# stm8.net
KiCad netlist of a schematic drawn in Altium Designer
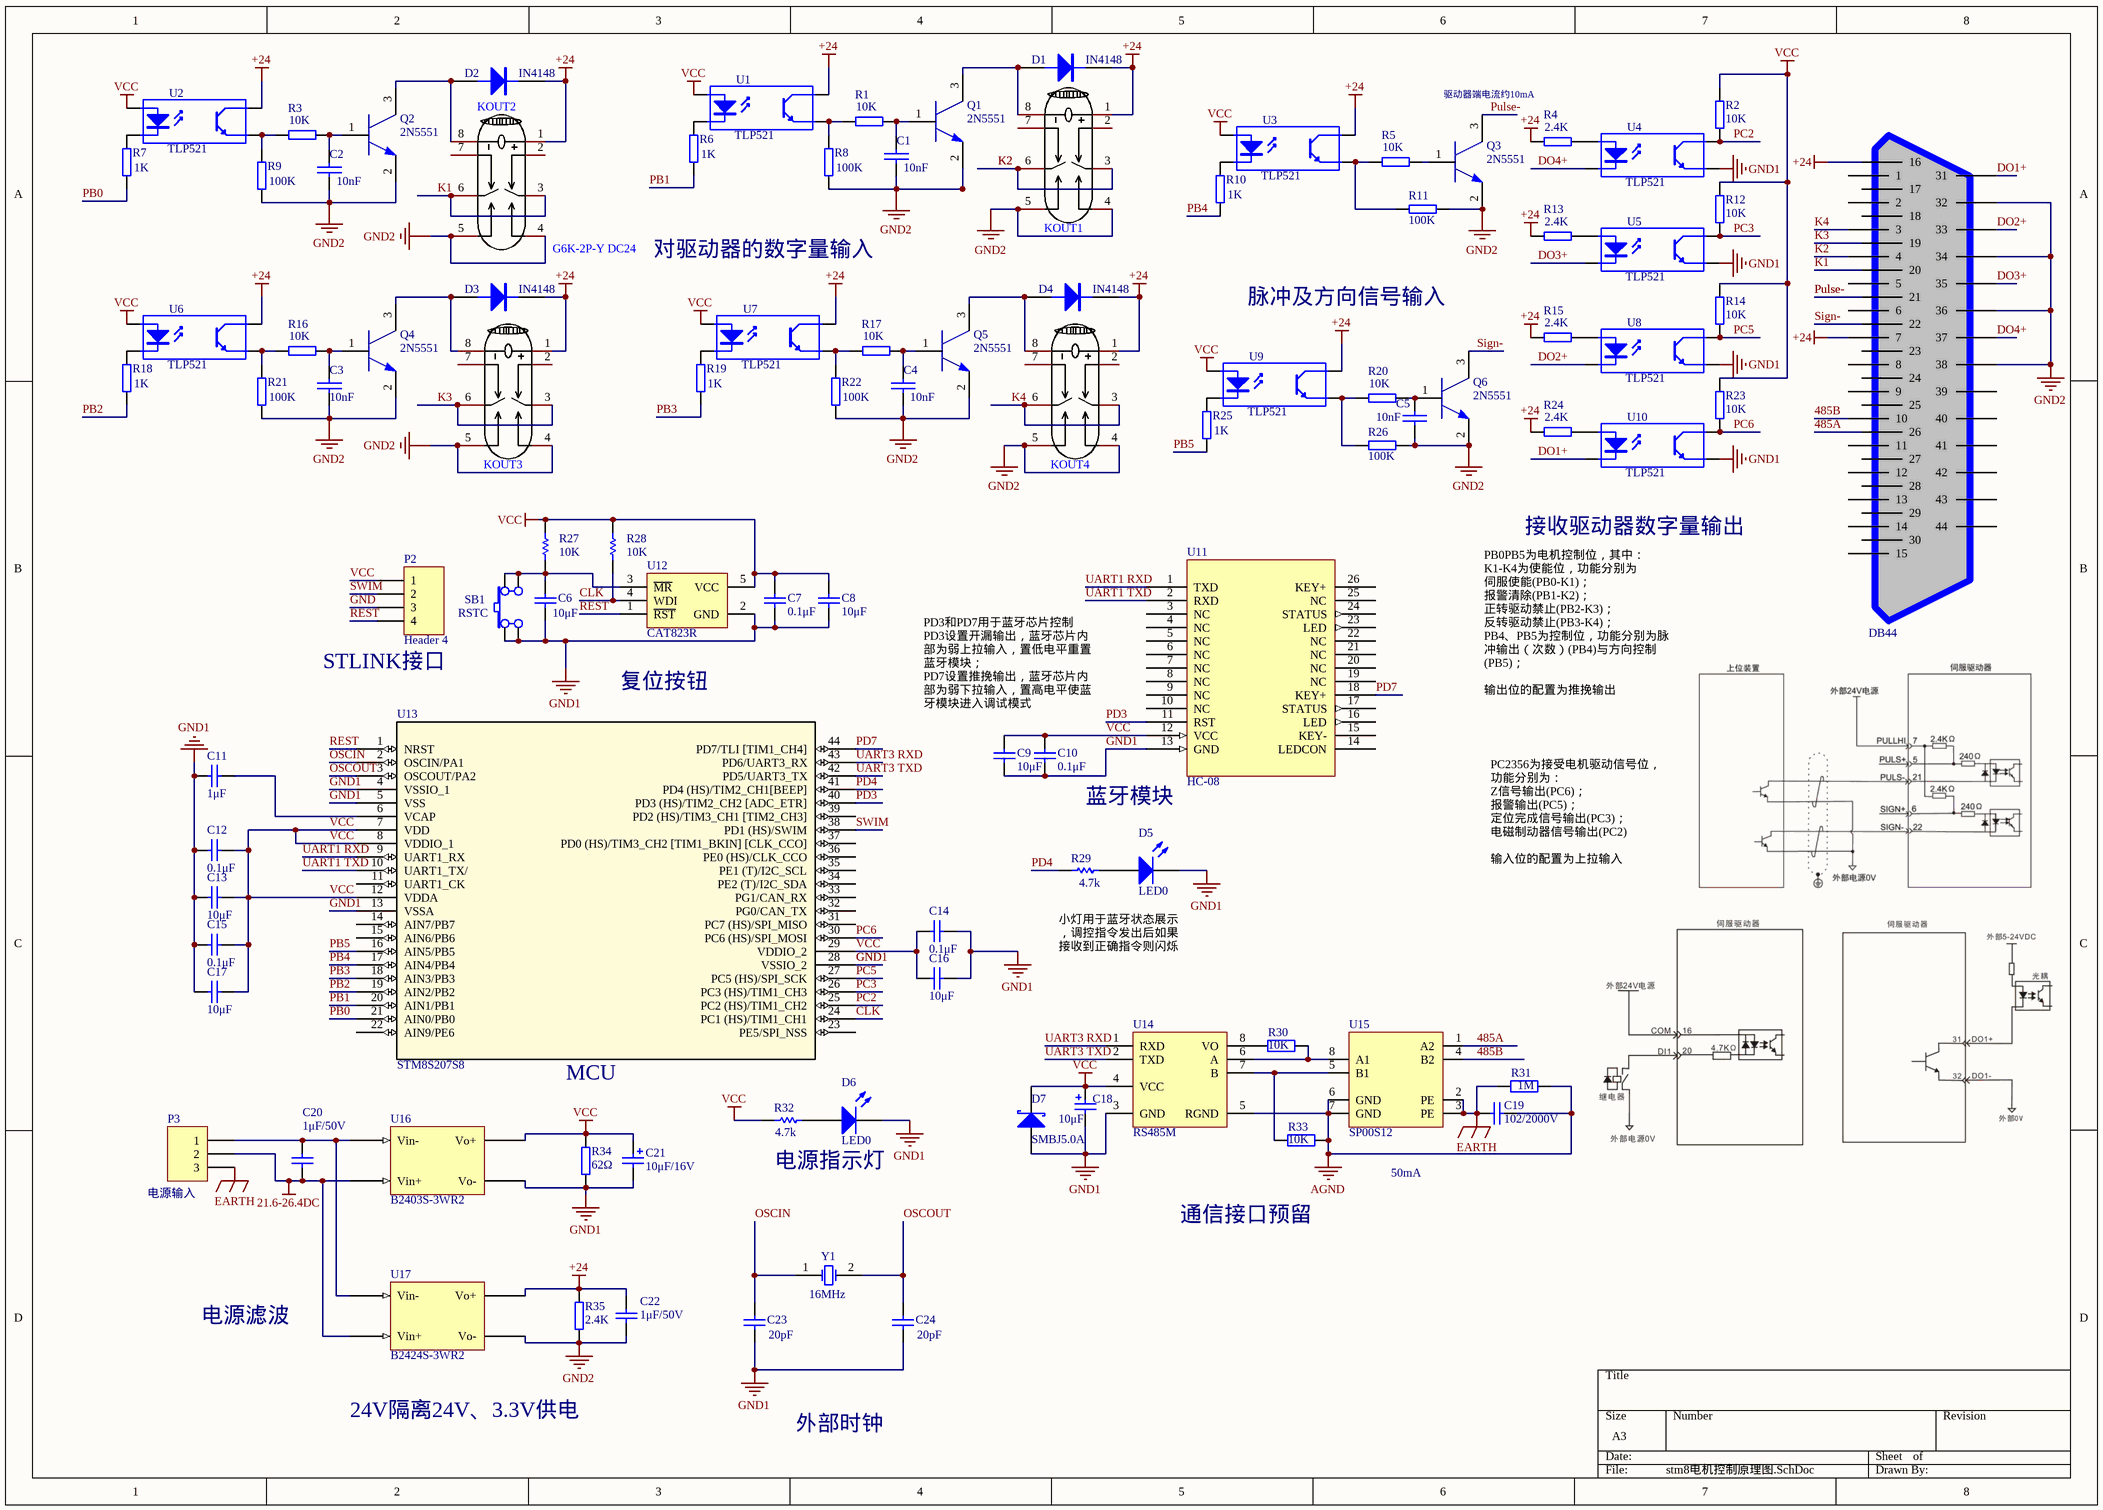
[diagram p0: stm8电机控制原理图.SchDoc]

(export (version "E")
  (design (tool "Eeschema 10.0.6"))
  (components
    (comp (ref "C1")
      (value "10nF")
      (footprint "C 0603_L")
      (description "Capacitor")
      (libsource (lib "*") (part "CAP"))
    )
    (comp (ref "C2")
      (value "10nF")
      (footprint "C 0603_L")
      (description "Capacitor")
      (libsource (lib "*") (part "CAP"))
    )
    (comp (ref "C3")
      (value "10nF")
      (footprint "C 0603_L")
      (description "Capacitor")
      (libsource (lib "*") (part "CAP"))
    )
    (comp (ref "C4")
      (value "10nF")
      (footprint "C 0603_L")
      (description "Capacitor")
      (libsource (lib "*") (part "CAP"))
    )
    (comp (ref "C5")
      (value "10nF")
      (footprint "C 0603_L")
      (description "Capacitor")
      (libsource (lib "*") (part "CAP"))
    )
    (comp (ref "C6")
      (value "10μF")
      (footprint "C 0603_L")
      (description "Capacitor")
      (fields (field (name "PUBLISHER") "Altium Limited"))
      (libsource (lib "Miscellaneous Devices") (part "Cap"))
    )
    (comp (ref "C7")
      (value "0.1μF")
      (footprint "C 0603_L")
      (description "Capacitor")
      (fields (field (name "PUBLISHER") "Altium Limited"))
      (libsource (lib "Miscellaneous Devices") (part "Cap"))
    )
    (comp (ref "C8")
      (value "10μF")
      (footprint "C 0603_L")
      (description "Capacitor")
      (fields (field (name "PUBLISHER") "Altium Limited"))
      (libsource (lib "Miscellaneous Devices") (part "Cap"))
    )
    (comp (ref "C9")
      (value "10μF")
      (footprint "C 0603_L")
      (description "Capacitor")
      (fields (field (name "PUBLISHER") "Altium Limited"))
      (libsource (lib "Miscellaneous Devices") (part "Cap"))
    )
    (comp (ref "C10")
      (value "0.1μF")
      (footprint "C 0603_L")
      (description "Capacitor")
      (fields (field (name "PUBLISHER") "Altium Limited"))
      (libsource (lib "Miscellaneous Devices") (part "Cap"))
    )
    (comp (ref "C11")
      (value "1μF")
      (footprint "C 0603_L")
      (description "Capacitor")
      (fields (field (name "PUBLISHER") "Altium Limited"))
      (libsource (lib "Miscellaneous Devices") (part "Cap"))
    )
    (comp (ref "C12")
      (value "0.1μF")
      (footprint "C 0603_L")
      (description "Capacitor")
      (fields (field (name "PUBLISHER") "Altium Limited"))
      (libsource (lib "Miscellaneous Devices") (part "Cap"))
    )
    (comp (ref "C13")
      (value "10μF")
      (footprint "C 0603_L")
      (description "Capacitor")
      (fields (field (name "PUBLISHER") "Altium Limited"))
      (libsource (lib "Miscellaneous Devices") (part "Cap"))
    )
    (comp (ref "C14")
      (value "0.1μF")
      (footprint "C 0603_L")
      (description "Capacitor")
      (fields (field (name "PUBLISHER") "Altium Limited"))
      (libsource (lib "Miscellaneous Devices") (part "Cap"))
    )
    (comp (ref "C15")
      (value "0.1μF")
      (footprint "C 0603_L")
      (description "Capacitor")
      (fields (field (name "PUBLISHER") "Altium Limited"))
      (libsource (lib "Miscellaneous Devices") (part "Cap"))
    )
    (comp (ref "C16")
      (value "10μF")
      (footprint "C 0603_L")
      (description "Capacitor")
      (fields (field (name "PUBLISHER") "Altium Limited"))
      (libsource (lib "Miscellaneous Devices") (part "Cap"))
    )
    (comp (ref "C17")
      (value "10μF")
      (footprint "C 0603_L")
      (description "Capacitor")
      (fields (field (name "PUBLISHER") "Altium Limited"))
      (libsource (lib "Miscellaneous Devices") (part "Cap"))
    )
    (comp (ref "C18")
      (value "10μF")
      (footprint "C 0603_L")
      (description "Polarized Capacitor (Radial)")
      (fields (field (name "PUBLISHER") "Altium Limited"))
      (libsource (lib "Miscellaneous Devices") (part "Cap Pol1"))
    )
    (comp (ref "C19")
      (value "102/2000V")
      (footprint "RAD0.6")
      (description "Capacitor")
      (fields (field (name "PUBLISHER") "Altium Limited"))
      (libsource (lib "Miscellaneous Devices") (part "Cap"))
    )
    (comp (ref "C20")
      (value "1μF/50V")
      (footprint "C 1206_L")
      (description "Capacitor")
      (fields (field (name "PUBLISHER") "Altium Limited"))
      (libsource (lib "Miscellaneous Devices") (part "Cap"))
    )
    (comp (ref "C21")
      (value "10μF/16V")
      (footprint "SMD-EC-F4")
      (description "Polarized Capacitor (Axial)")
      (fields (field (name "Comment") "Cap Pol2") (field (name "PUBLISHER") "Altium Limited"))
      (libsource (lib "Miscellaneous Devices") (part "Cap Pol2"))
    )
    (comp (ref "C22")
      (value "1μF/50V")
      (footprint "C 1206_L")
      (description "Capacitor")
      (fields (field (name "PUBLISHER") "Altium Limited"))
      (libsource (lib "Miscellaneous Devices") (part "Cap"))
    )
    (comp (ref "C23")
      (value "20pF")
      (footprint "C 0603_L")
      (description "Capacitor")
      (fields (field (name "PUBLISHER") "Altium Limited"))
      (libsource (lib "Miscellaneous Devices") (part "Cap"))
    )
    (comp (ref "C24")
      (value "20pF")
      (footprint "C 0603_L")
      (description "Capacitor")
      (fields (field (name "PUBLISHER") "Altium Limited"))
      (libsource (lib "Miscellaneous Devices") (part "Cap"))
    )
    (comp (ref "D1")
      (value "IN4148")
      (footprint "DO-214AC")
      (description "Diode")
      (libsource (lib "*") (part "DIODE"))
    )
    (comp (ref "D2")
      (value "IN4148")
      (footprint "DO-214AC")
      (description "Diode")
      (libsource (lib "*") (part "DIODE"))
    )
    (comp (ref "D3")
      (value "IN4148")
      (footprint "DO-214AC")
      (description "Diode")
      (libsource (lib "*") (part "DIODE"))
    )
    (comp (ref "D4")
      (value "IN4148")
      (footprint "DO-214AC")
      (description "Diode")
      (libsource (lib "*") (part "DIODE"))
    )
    (comp (ref "D5")
      (value "LED0")
      (footprint "LED 0603R")
      (description "Typical INFRARED GaAs LED")
      (fields (field (name "PUBLISHER") "Altium Limited"))
      (libsource (lib "Miscellaneous Devices") (part "LED0"))
    )
    (comp (ref "D6")
      (value "LED0")
      (footprint "LED 0603R")
      (description "Typical INFRARED GaAs LED")
      (fields (field (name "PUBLISHER") "Altium Limited"))
      (libsource (lib "Miscellaneous Devices") (part "LED0"))
    )
    (comp (ref "D7")
      (value "SMBJ5.0A")
      (footprint "DO-214AA")
      (description "Schottky Diode")
      (fields (field (name "PUBLISHER") "Altium Limited"))
      (libsource (lib "Miscellaneous Devices") (part "D Schottky"))
    )
    (comp (ref "KOUT1")
      (value "G6K-2P-Y DC24")
      (footprint "RELAY-TH_G6K-2P-Y")
      (fields (field (name "MANUFACTURER") "OMRON(欧姆龙)"))
      (libsource (lib "altium-import") (part "root_3_mirrored_G6K-2P-Y DC24_"))
    )
    (comp (ref "KOUT2")
      (value "G6K-2P-Y DC24")
      (footprint "RELAY-TH_G6K-2P-Y")
      (fields (field (name "MANUFACTURER") "OMRON(欧姆龙)"))
      (libsource (lib "altium-import") (part "root_3_mirrored_G6K-2P-Y DC24_"))
    )
    (comp (ref "KOUT3")
      (value "G6K-2P-Y DC24")
      (footprint "RELAY-TH_G6K-2P-Y")
      (fields (field (name "MANUFACTURER") "OMRON(欧姆龙)"))
      (libsource (lib "altium-import") (part "root_3_mirrored_G6K-2P-Y DC24_"))
    )
    (comp (ref "KOUT4")
      (value "G6K-2P-Y DC24")
      (footprint "RELAY-TH_G6K-2P-Y")
      (fields (field (name "MANUFACTURER") "OMRON(欧姆龙)"))
      (libsource (lib "altium-import") (part "root_3_mirrored_G6K-2P-Y DC24_"))
    )
    (comp (ref "P1")
      (value "DB44")
      (footprint "DSUB-TH_DS1038-44FBNSIA74-0CC")
      (libsource (lib "stm8电机控制原理图") (part "DB44_1"))
    )
    (comp (ref "P2")
      (value "Header 4")
      (footprint "XH2.54-LI-4P")
      (description "Header, 4-Pin")
      (fields (field (name "PUBLISHER") "Altium Limited"))
      (libsource (lib "Miscellaneous Connectors") (part "Header 4"))
    )
    (comp (ref "P3")
      (value "电源输入")
      (footprint "3PDZ")
      (description "Header, 3-Pin")
      (fields (field (name "PUBLISHER") "Altium Limited"))
      (libsource (lib "Miscellaneous Connectors") (part "Header 3"))
    )
    (comp (ref "Q1") (value "2N5551") (footprint "SOT-23") (libsource (lib "YXH1") (part "9014")))
    (comp (ref "Q2") (value "2N5551") (footprint "SOT-23") (libsource (lib "YXH1") (part "9014")))
    (comp (ref "Q3") (value "2N5551") (footprint "SOT-23") (libsource (lib "YXH1") (part "9014")))
    (comp (ref "Q4") (value "2N5551") (footprint "SOT-23") (libsource (lib "YXH1") (part "9014")))
    (comp (ref "Q5") (value "2N5551") (footprint "SOT-23") (libsource (lib "YXH1") (part "9014")))
    (comp (ref "Q6") (value "2N5551") (footprint "SOT-23") (libsource (lib "YXH1") (part "9014")))
    (comp (ref "R1") (value "10K") (footprint "R 0603_L") (libsource (lib "*") (part "RES2")))
    (comp (ref "R2") (value "10K") (footprint "R 0603_L") (libsource (lib "*") (part "RES2")))
    (comp (ref "R3") (value "10K") (footprint "R 0603_L") (libsource (lib "*") (part "RES2")))
    (comp (ref "R4") (value "2.4K") (footprint "R 0603_L") (libsource (lib "*") (part "RES2")))
    (comp (ref "R5") (value "10K") (footprint "R 0603_L") (libsource (lib "*") (part "RES2")))
    (comp (ref "R6") (value "1K") (footprint "R 0603_L") (libsource (lib "*") (part "RES2")))
    (comp (ref "R7") (value "1K") (footprint "R 0603_L") (libsource (lib "*") (part "RES2")))
    (comp (ref "R8") (value "100K") (footprint "R 0603_L") (libsource (lib "*") (part "RES2")))
    (comp (ref "R9") (value "100K") (footprint "R 0603_L") (libsource (lib "*") (part "RES2")))
    (comp (ref "R10") (value "1K") (footprint "R 0603_L") (libsource (lib "*") (part "RES2")))
    (comp (ref "R11") (value "100K") (footprint "R 0603_L") (libsource (lib "*") (part "RES2")))
    (comp (ref "R12") (value "10K") (footprint "R 0603_L") (libsource (lib "*") (part "RES2")))
    (comp (ref "R13") (value "2.4K") (footprint "R 0603_L") (libsource (lib "*") (part "RES2")))
    (comp (ref "R14") (value "10K") (footprint "R 0603_L") (libsource (lib "*") (part "RES2")))
    (comp (ref "R15") (value "2.4K") (footprint "R 0603_L") (libsource (lib "*") (part "RES2")))
    (comp (ref "R16") (value "10K") (footprint "R 0603_L") (libsource (lib "*") (part "RES2")))
    (comp (ref "R17") (value "10K") (footprint "R 0603_L") (libsource (lib "*") (part "RES2")))
    (comp (ref "R18") (value "1K") (footprint "R 0603_L") (libsource (lib "*") (part "RES2")))
    (comp (ref "R19") (value "1K") (footprint "R 0603_L") (libsource (lib "*") (part "RES2")))
    (comp (ref "R20") (value "10K") (footprint "R 0603_L") (libsource (lib "*") (part "RES2")))
    (comp (ref "R21") (value "100K") (footprint "R 0603_L") (libsource (lib "*") (part "RES2")))
    (comp (ref "R22") (value "100K") (footprint "R 0603_L") (libsource (lib "*") (part "RES2")))
    (comp (ref "R23") (value "10K") (footprint "R 0603_L") (libsource (lib "*") (part "RES2")))
    (comp (ref "R24") (value "2.4K") (footprint "R 0603_L") (libsource (lib "*") (part "RES2")))
    (comp (ref "R25") (value "1K") (footprint "R 0603_L") (libsource (lib "*") (part "RES2")))
    (comp (ref "R26") (value "100K") (footprint "R 0603_L") (libsource (lib "*") (part "RES2")))
    (comp (ref "R27")
      (value "10K")
      (footprint "R 0603_L")
      (description "Resistor")
      (fields (field (name "PUBLISHER") "Altium Limited"))
      (libsource (lib "Miscellaneous Devices") (part "Res1"))
    )
    (comp (ref "R28")
      (value "10K")
      (footprint "R 0603_L")
      (description "Resistor")
      (fields (field (name "PUBLISHER") "Altium Limited"))
      (libsource (lib "Miscellaneous Devices") (part "Res1"))
    )
    (comp (ref "R29")
      (value "4.7k")
      (footprint "R 0603_L")
      (description "Resistor")
      (fields (field (name "PUBLISHER") "Altium Limited"))
      (libsource (lib "Miscellaneous Devices") (part "Res1"))
    )
    (comp (ref "R30")
      (value "10K")
      (footprint "R 0603_L")
      (description "Resistor")
      (fields (field (name "PUBLISHER") "Altium Limited"))
      (libsource (lib "Miscellaneous Devices") (part "Res2"))
    )
    (comp (ref "R31")
      (value "1M")
      (footprint "R 2512_L")
      (description "Resistor")
      (fields (field (name "PUBLISHER") "Altium Limited"))
      (libsource (lib "Miscellaneous Devices") (part "Res2"))
    )
    (comp (ref "R32")
      (value "4.7k")
      (footprint "R 0603_L")
      (description "Resistor")
      (fields (field (name "PUBLISHER") "Altium Limited"))
      (libsource (lib "Miscellaneous Devices") (part "Res1"))
    )
    (comp (ref "R33")
      (value "10K")
      (footprint "R 0603_L")
      (description "Resistor")
      (fields (field (name "PUBLISHER") "Altium Limited"))
      (libsource (lib "Miscellaneous Devices") (part "Res2"))
    )
    (comp (ref "R34") (value "62Ω") (footprint "R 2512_L") (libsource (lib "*") (part "RES2")))
    (comp (ref "R35") (value "2.4K") (footprint "R 2512_L") (libsource (lib "*") (part "RES2")))
    (comp (ref "SB1") (value "RSTC") (footprint "按键4P") (libsource (lib "YXH1") (part "SW-TACT")))
    (comp (ref "U1") (value "TLP521") (footprint "SMD521-1") (libsource (lib "YXH1") (part "TLP521")))
    (comp (ref "U2") (value "TLP521") (footprint "SMD521-1") (libsource (lib "YXH1") (part "TLP521")))
    (comp (ref "U3") (value "TLP521") (footprint "SMD521-1") (libsource (lib "YXH1") (part "TLP521")))
    (comp (ref "U4") (value "TLP521") (footprint "SMD521-1") (libsource (lib "YXH1") (part "TLP521")))
    (comp (ref "U5") (value "TLP521") (footprint "SMD521-1") (libsource (lib "YXH1") (part "TLP521")))
    (comp (ref "U6") (value "TLP521") (footprint "SMD521-1") (libsource (lib "YXH1") (part "TLP521")))
    (comp (ref "U7") (value "TLP521") (footprint "SMD521-1") (libsource (lib "YXH1") (part "TLP521")))
    (comp (ref "U8") (value "TLP521") (footprint "SMD521-1") (libsource (lib "YXH1") (part "TLP521")))
    (comp (ref "U9") (value "TLP521") (footprint "SMD521-1") (libsource (lib "YXH1") (part "TLP521")))
    (comp (ref "U10") (value "TLP521") (footprint "SMD521-1") (libsource (lib "YXH1") (part "TLP521")))
    (comp (ref "U11")
      (value "HC-08")
      (footprint "HC-22/08/42新_SMT2")
      (libsource (lib "Bluetooth") (part "Bluetooth"))
    )
    (comp (ref "U12") (value "CAT823R") (footprint "SOT23-5") (libsource (lib "YXH1") (part "CAT823")))
    (comp (ref "U13")
      (value "STM8S207S8")
      (footprint "LQFP-44")
      (description "No Description Available")
      (fields
        (field (name "MANUFACTURER_PART_NUMBER") "STM8S208S8T6")
        (field (name "COPYRIGHT") "Copyright (C) 2022 Ultra Librarian. All rights reserved.")
      )
      (libsource (lib "STM8S208S8T6") (part "STM8S208S8T6"))
    )
    (comp (ref "U14") (value "RS485M") (footprint "RS485M") (libsource (lib "YXH1") (part "RS485M")))
    (comp (ref "U15") (value "SP00S12") (footprint "RS485M") (libsource (lib "YXH1") (part "SP00S12")))
    (comp (ref "U16")
      (value "B2403S-3WR2")
      (footprint "B2403S-2WR3")
      (libsource (lib "Bluetooth") (part "isolation"))
    )
    (comp (ref "U17")
      (value "B2424S-3WR2")
      (footprint "B2403S-2WR3")
      (libsource (lib "stm8电机控制原理图") (part "B2403S-2W3R"))
    )
    (comp (ref "Y1")
      (value "16MHz")
      (footprint "SMD-5032_2P")
      (description "Crystal Oscillator")
      (fields (field (name "PUBLISHER") "Altium Limited"))
      (libsource (lib "Miscellaneous Devices") (part "XTAL"))
    )
  )
  (nets
    (net (code "1") (name "+24") (class "Default")
      (node (ref "C22") (pin "2") (pinfunction "2_2") (pintype "passive"))
      (node (ref "D1") (pin "2") (pinfunction "K_2") (pintype "passive"))
      (node (ref "D2") (pin "2") (pinfunction "K_2") (pintype "passive"))
      (node (ref "D3") (pin "2") (pinfunction "K_2") (pintype "passive"))
      (node (ref "D4") (pin "2") (pinfunction "K_2") (pintype "passive"))
      (node (ref "KOUT1") (pin "1") (pinfunction "1_1") (pintype "passive"))
      (node (ref "KOUT2") (pin "1") (pinfunction "1_1") (pintype "passive"))
      (node (ref "KOUT3") (pin "1") (pinfunction "1_1") (pintype "passive"))
      (node (ref "KOUT4") (pin "1") (pinfunction "1_1") (pintype "passive"))
      (node (ref "P1") (pin "16") (pinfunction "16_16") (pintype "passive"))
      (node (ref "P1") (pin "7") (pinfunction "7_7") (pintype "passive"))
      (node (ref "R13") (pin "2") (pinfunction "2_2") (pintype "passive"))
      (node (ref "R15") (pin "2") (pinfunction "2_2") (pintype "passive"))
      (node (ref "R24") (pin "2") (pinfunction "2_2") (pintype "passive"))
      (node (ref "R35") (pin "1") (pinfunction "1_1") (pintype "passive"))
      (node (ref "R4") (pin "2") (pinfunction "2_2") (pintype "passive"))
      (node (ref "U1") (pin "4") (pinfunction "C_4") (pintype "passive"))
      (node (ref "U17") (pin "4") (pinfunction "Vo+_4") (pintype "power_in"))
      (node (ref "U2") (pin "4") (pinfunction "C_4") (pintype "passive"))
      (node (ref "U3") (pin "4") (pinfunction "C_4") (pintype "passive"))
      (node (ref "U6") (pin "4") (pinfunction "C_4") (pintype "passive"))
      (node (ref "U7") (pin "4") (pinfunction "C_4") (pintype "passive"))
      (node (ref "U9") (pin "4") (pinfunction "C_4") (pintype "passive"))
    )
    (net (code "2") (name "/485A") (class "Default")
      (node (ref "P1") (pin "26") (pinfunction "26_26") (pintype "passive"))
      (node (ref "U15") (pin "1") (pinfunction "A2_1") (pintype "passive"))
    )
    (net (code "3") (name "/485B") (class "Default")
      (node (ref "P1") (pin "10") (pinfunction "10_10") (pintype "passive"))
      (node (ref "U15") (pin "4") (pinfunction "B2_4") (pintype "passive"))
    )
    (net (code "4") (name "/CLK") (class "Default")
      (node (ref "R28") (pin "2") (pinfunction "2_2") (pintype "passive"))
      (node (ref "U12") (pin "4") (pinfunction "WDI_4") (pintype "passive"))
      (node (ref "U13") (pin "24") (pinfunction "PC1_(HS)/TIM1_CH1_24") (pintype "bidirectional"))
    )
    (net (code "5") (name "/DO1+") (class "Default")
      (node (ref "P1") (pin "31") (pinfunction "31_31") (pintype "passive"))
      (node (ref "U10") (pin "2") (pinfunction "K_2") (pintype "passive"))
    )
    (net (code "6") (name "/DO2+") (class "Default")
      (node (ref "P1") (pin "33") (pinfunction "33_33") (pintype "passive"))
      (node (ref "U8") (pin "2") (pinfunction "K_2") (pintype "passive"))
    )
    (net (code "7") (name "/DO3+") (class "Default")
      (node (ref "P1") (pin "35") (pinfunction "35_35") (pintype "passive"))
      (node (ref "U5") (pin "2") (pinfunction "K_2") (pintype "passive"))
    )
    (net (code "8") (name "/DO4+") (class "Default")
      (node (ref "P1") (pin "37") (pinfunction "37_37") (pintype "passive"))
      (node (ref "U4") (pin "2") (pinfunction "K_2") (pintype "passive"))
    )
    (net (code "9") (name "/K1") (class "Default")
      (node (ref "KOUT2") (pin "3") (pinfunction "3_3") (pintype "passive"))
      (node (ref "KOUT2") (pin "6") (pinfunction "6_6") (pintype "passive"))
      (node (ref "P1") (pin "20") (pinfunction "20_20") (pintype "passive"))
    )
    (net (code "10") (name "/K2") (class "Default")
      (node (ref "KOUT1") (pin "3") (pinfunction "3_3") (pintype "passive"))
      (node (ref "KOUT1") (pin "6") (pinfunction "6_6") (pintype "passive"))
      (node (ref "P1") (pin "4") (pinfunction "4_4") (pintype "passive"))
    )
    (net (code "11") (name "/K3") (class "Default")
      (node (ref "KOUT3") (pin "3") (pinfunction "3_3") (pintype "passive"))
      (node (ref "KOUT3") (pin "6") (pinfunction "6_6") (pintype "passive"))
      (node (ref "P1") (pin "19") (pinfunction "19_19") (pintype "passive"))
    )
    (net (code "12") (name "/K4") (class "Default")
      (node (ref "KOUT4") (pin "3") (pinfunction "3_3") (pintype "passive"))
      (node (ref "KOUT4") (pin "6") (pinfunction "6_6") (pintype "passive"))
      (node (ref "P1") (pin "3") (pinfunction "3_3") (pintype "passive"))
    )
    (net (code "13") (name "/OSCIN") (class "Default")
      (node (ref "C23") (pin "2") (pinfunction "2_2") (pintype "passive"))
      (node (ref "U13") (pin "2") (pinfunction "OSCIN/PA1_2") (pintype "bidirectional"))
      (node (ref "Y1") (pin "1") (pinfunction "OSC1_1") (pintype "passive"))
    )
    (net (code "14") (name "/OSCOUT") (class "Default")
      (node (ref "C24") (pin "2") (pinfunction "2_2") (pintype "passive"))
      (node (ref "U13") (pin "3") (pinfunction "OSCOUT/PA2_3") (pintype "bidirectional"))
      (node (ref "Y1") (pin "2") (pinfunction "OSC2_2") (pintype "passive"))
    )
    (net (code "15") (name "/PB0") (class "Default")
      (node (ref "R7") (pin "1") (pinfunction "1_1") (pintype "passive"))
      (node (ref "U13") (pin "21") (pinfunction "AIN0/PB0_21") (pintype "bidirectional"))
    )
    (net (code "16") (name "/PB1") (class "Default")
      (node (ref "R6") (pin "1") (pinfunction "1_1") (pintype "passive"))
      (node (ref "U13") (pin "20") (pinfunction "AIN1/PB1_20") (pintype "bidirectional"))
    )
    (net (code "17") (name "/PB2") (class "Default")
      (node (ref "R18") (pin "1") (pinfunction "1_1") (pintype "passive"))
      (node (ref "U13") (pin "19") (pinfunction "AIN2/PB2_19") (pintype "bidirectional"))
    )
    (net (code "18") (name "/PB3") (class "Default")
      (node (ref "R19") (pin "1") (pinfunction "1_1") (pintype "passive"))
      (node (ref "U13") (pin "18") (pinfunction "AIN3/PB3_18") (pintype "bidirectional"))
    )
    (net (code "19") (name "/PB4") (class "Default")
      (node (ref "R10") (pin "1") (pinfunction "1_1") (pintype "passive"))
      (node (ref "U13") (pin "17") (pinfunction "AIN4/PB4_17") (pintype "bidirectional"))
    )
    (net (code "20") (name "/PB5") (class "Default")
      (node (ref "R25") (pin "1") (pinfunction "1_1") (pintype "passive"))
      (node (ref "U13") (pin "16") (pinfunction "AIN5/PB5_16") (pintype "bidirectional"))
    )
    (net (code "21") (name "/PC2") (class "Default")
      (node (ref "R2") (pin "2") (pinfunction "2_2") (pintype "passive"))
      (node (ref "U13") (pin "25") (pinfunction "PC2_(HS)/TIM1_CH2_25") (pintype "bidirectional"))
      (node (ref "U4") (pin "4") (pinfunction "C_4") (pintype "passive"))
    )
    (net (code "22") (name "/PC3") (class "Default")
      (node (ref "R12") (pin "2") (pinfunction "2_2") (pintype "passive"))
      (node (ref "U13") (pin "26") (pinfunction "PC3_(HS)/TIM1_CH3_26") (pintype "bidirectional"))
      (node (ref "U5") (pin "4") (pinfunction "C_4") (pintype "passive"))
    )
    (net (code "23") (name "/PC5") (class "Default")
      (node (ref "R14") (pin "2") (pinfunction "2_2") (pintype "passive"))
      (node (ref "U13") (pin "27") (pinfunction "PC5_(HS)/SPI_SCK_27") (pintype "bidirectional"))
      (node (ref "U8") (pin "4") (pinfunction "C_4") (pintype "passive"))
    )
    (net (code "24") (name "/PC6") (class "Default")
      (node (ref "R23") (pin "2") (pinfunction "2_2") (pintype "passive"))
      (node (ref "U10") (pin "4") (pinfunction "C_4") (pintype "passive"))
      (node (ref "U13") (pin "30") (pinfunction "PC6_(HS)/SPI_MOSI_30") (pintype "bidirectional"))
    )
    (net (code "25") (name "/PD3") (class "Default")
      (node (ref "U11") (pin "11") (pinfunction "RST_11") (pintype "passive"))
      (node (ref "U13") (pin "40") (pinfunction "PD3_(HS)/TIM2_CH2_[ADC_ETR]_40") (pintype "bidirectional"))
    )
    (net (code "26") (name "/PD4") (class "Default")
      (node (ref "R29") (pin "1") (pinfunction "1_1") (pintype "passive"))
      (node (ref "U13") (pin "41") (pinfunction "PD4_(HS)/TIM2_CH1[BEEP]_41") (pintype "bidirectional"))
    )
    (net (code "27") (name "/PD7") (class "Default")
      (node (ref "U11") (pin "18") (pinfunction "KEY+_18") (pintype "passive"))
      (node (ref "U13") (pin "44") (pinfunction "PD7/TLI_[TIM1_CH4]_44") (pintype "bidirectional"))
    )
    (net (code "28") (name "/Pulse") (class "Default")
      (node (ref "P1") (pin "21") (pinfunction "21_21") (pintype "passive"))
      (node (ref "Q3") (pin "3") (pinfunction "c_3") (pintype "passive"))
    )
    (net (code "29") (name "/REST") (class "Default")
      (node (ref "P2") (pin "4") (pinfunction "4_4") (pintype "passive"))
      (node (ref "U12") (pin "1") (pinfunction "~{RST}_1") (pintype "passive"))
      (node (ref "U13") (pin "1") (pinfunction "NRST_1") (pintype "bidirectional"))
    )
    (net (code "30") (name "/SWIM") (class "Default")
      (node (ref "P2") (pin "2") (pinfunction "2_2") (pintype "passive"))
      (node (ref "U13") (pin "38") (pinfunction "PD1_(HS)/SWIM_38") (pintype "bidirectional"))
    )
    (net (code "31") (name "/Sign-") (class "Default")
      (node (ref "P1") (pin "22") (pinfunction "22_22") (pintype "passive"))
      (node (ref "Q6") (pin "3") (pinfunction "c_3") (pintype "passive"))
    )
    (net (code "32") (name "/UART1 RXD") (class "Default")
      (node (ref "U11") (pin "1") (pinfunction "TXD_1") (pintype "passive"))
      (node (ref "U13") (pin "9") (pinfunction "UART1_RX_9") (pintype "bidirectional"))
    )
    (net (code "33") (name "/UART1 TXD") (class "Default")
      (node (ref "U11") (pin "2") (pinfunction "RXD_2") (pintype "passive"))
      (node (ref "U13") (pin "10") (pinfunction "UART1_TX/_10") (pintype "bidirectional"))
    )
    (net (code "34") (name "/UART3 RXD") (class "Default")
      (node (ref "U13") (pin "43") (pinfunction "PD6/UART3_RX_43") (pintype "bidirectional"))
      (node (ref "U14") (pin "1") (pinfunction "RXD_1") (pintype "passive"))
    )
    (net (code "35") (name "/UART3 TXD") (class "Default")
      (node (ref "U13") (pin "42") (pinfunction "PD5/UART3_TX_42") (pintype "bidirectional"))
      (node (ref "U14") (pin "2") (pinfunction "TXD_2") (pintype "passive"))
    )
    (net (code "36") (name "21.6-26.4DC") (class "Default")
      (node (ref "C20") (pin "1") (pinfunction "1_1") (pintype "passive"))
      (node (ref "P3") (pin "2") (pinfunction "2_2") (pintype "passive"))
      (node (ref "U16") (pin "1") (pinfunction "Vin+_1") (pintype "input"))
      (node (ref "U17") (pin "1") (pinfunction "Vin+_1") (pintype "input"))
    )
    (net (code "37") (name "AGND") (class "Default")
      (node (ref "C19") (pin "1") (pinfunction "1_1") (pintype "passive"))
      (node (ref "R31") (pin "1") (pinfunction "1_1") (pintype "passive"))
      (node (ref "R33") (pin "1") (pinfunction "1_1") (pintype "passive"))
      (node (ref "U14") (pin "5") (pinfunction "RGND_5") (pintype "passive"))
      (node (ref "U15") (pin "6") (pinfunction "GND_6") (pintype "passive"))
      (node (ref "U15") (pin "7") (pinfunction "GND_7") (pintype "passive"))
    )
    (net (code "38") (name "EARTH") (class "Default")
      (node (ref "C19") (pin "2") (pinfunction "2_2") (pintype "passive"))
      (node (ref "P3") (pin "3") (pinfunction "3_3") (pintype "passive"))
      (node (ref "R31") (pin "2") (pinfunction "2_2") (pintype "passive"))
      (node (ref "U15") (pin "2") (pinfunction "PE_2") (pintype "passive"))
      (node (ref "U15") (pin "3") (pinfunction "PE_3") (pintype "passive"))
    )
    (net (code "39") (name "GND1") (class "Default")
      (node (ref "C10") (pin "1") (pinfunction "1_1") (pintype "passive"))
      (node (ref "C11") (pin "1") (pinfunction "1_1") (pintype "passive"))
      (node (ref "C12") (pin "1") (pinfunction "1_1") (pintype "passive"))
      (node (ref "C13") (pin "1") (pinfunction "1_1") (pintype "passive"))
      (node (ref "C14") (pin "2") (pinfunction "2_2") (pintype "passive"))
      (node (ref "C15") (pin "1") (pinfunction "1_1") (pintype "passive"))
      (node (ref "C16") (pin "2") (pinfunction "2_2") (pintype "passive"))
      (node (ref "C17") (pin "1") (pinfunction "1_1") (pintype "passive"))
      (node (ref "C18") (pin "2") (pinfunction "2_2") (pintype "passive"))
      (node (ref "C21") (pin "2") (pinfunction "2_2") (pintype "passive"))
      (node (ref "C23") (pin "1") (pinfunction "1_1") (pintype "passive"))
      (node (ref "C24") (pin "1") (pinfunction "1_1") (pintype "passive"))
      (node (ref "C6") (pin "2") (pinfunction "2_2") (pintype "passive"))
      (node (ref "C7") (pin "1") (pinfunction "1_1") (pintype "passive"))
      (node (ref "C8") (pin "1") (pinfunction "1_1") (pintype "passive"))
      (node (ref "C9") (pin "1") (pinfunction "1_1") (pintype "passive"))
      (node (ref "D5") (pin "2") (pinfunction "K_2") (pintype "passive"))
      (node (ref "D6") (pin "2") (pinfunction "K_2") (pintype "passive"))
      (node (ref "D7") (pin "1") (pinfunction "A_1") (pintype "passive"))
      (node (ref "P2") (pin "3") (pinfunction "3_3") (pintype "passive"))
      (node (ref "R34") (pin "2") (pinfunction "2_2") (pintype "passive"))
      (node (ref "SB1") (pin "1") (pinfunction "I2_1") (pintype "passive"))
      (node (ref "SB1") (pin "2") (pinfunction "I3_2") (pintype "passive"))
      (node (ref "U10") (pin "3") (pinfunction "E_3") (pintype "passive"))
      (node (ref "U11") (pin "13") (pinfunction "GND_13") (pintype "input"))
      (node (ref "U12") (pin "2") (pinfunction "GND_2") (pintype "passive"))
      (node (ref "U13") (pin "13") (pinfunction "VSSA_13") (pintype "passive"))
      (node (ref "U13") (pin "28") (pinfunction "VSSIO_2_28") (pintype "passive"))
      (node (ref "U13") (pin "4") (pinfunction "VSSIO_1_4") (pintype "passive"))
      (node (ref "U13") (pin "5") (pinfunction "VSS_5") (pintype "passive"))
      (node (ref "U14") (pin "3") (pinfunction "GND_3") (pintype "passive"))
      (node (ref "U16") (pin "3") (pinfunction "Vo-_3") (pintype "passive"))
      (node (ref "U4") (pin "3") (pinfunction "E_3") (pintype "passive"))
      (node (ref "U5") (pin "3") (pinfunction "E_3") (pintype "passive"))
      (node (ref "U8") (pin "3") (pinfunction "E_3") (pintype "passive"))
    )
    (net (code "40") (name "GND2") (class "Default")
      (node (ref "C1") (pin "2") (pinfunction "2_2") (pintype "passive"))
      (node (ref "C2") (pin "2") (pinfunction "2_2") (pintype "passive"))
      (node (ref "C22") (pin "1") (pinfunction "1_1") (pintype "passive"))
      (node (ref "C3") (pin "2") (pinfunction "2_2") (pintype "passive"))
      (node (ref "C4") (pin "2") (pinfunction "2_2") (pintype "passive"))
      (node (ref "C5") (pin "2") (pinfunction "2_2") (pintype "passive"))
      (node (ref "KOUT1") (pin "4") (pinfunction "4_4") (pintype "passive"))
      (node (ref "KOUT1") (pin "5") (pinfunction "5_5") (pintype "passive"))
      (node (ref "KOUT2") (pin "4") (pinfunction "4_4") (pintype "passive"))
      (node (ref "KOUT2") (pin "5") (pinfunction "5_5") (pintype "passive"))
      (node (ref "KOUT3") (pin "4") (pinfunction "4_4") (pintype "passive"))
      (node (ref "KOUT3") (pin "5") (pinfunction "5_5") (pintype "passive"))
      (node (ref "KOUT4") (pin "4") (pinfunction "4_4") (pintype "passive"))
      (node (ref "KOUT4") (pin "5") (pinfunction "5_5") (pintype "passive"))
      (node (ref "P1") (pin "32") (pinfunction "32_32") (pintype "passive"))
      (node (ref "P1") (pin "34") (pinfunction "34_34") (pintype "passive"))
      (node (ref "P1") (pin "36") (pinfunction "36_36") (pintype "passive"))
      (node (ref "P1") (pin "38") (pinfunction "38_38") (pintype "passive"))
      (node (ref "Q1") (pin "2") (pinfunction "e_2") (pintype "passive"))
      (node (ref "Q2") (pin "2") (pinfunction "e_2") (pintype "passive"))
      (node (ref "Q3") (pin "2") (pinfunction "e_2") (pintype "passive"))
      (node (ref "Q4") (pin "2") (pinfunction "e_2") (pintype "passive"))
      (node (ref "Q5") (pin "2") (pinfunction "e_2") (pintype "passive"))
      (node (ref "Q6") (pin "2") (pinfunction "e_2") (pintype "passive"))
      (node (ref "R11") (pin "1") (pinfunction "1_1") (pintype "passive"))
      (node (ref "R21") (pin "1") (pinfunction "1_1") (pintype "passive"))
      (node (ref "R22") (pin "1") (pinfunction "1_1") (pintype "passive"))
      (node (ref "R26") (pin "1") (pinfunction "1_1") (pintype "passive"))
      (node (ref "R35") (pin "2") (pinfunction "2_2") (pintype "passive"))
      (node (ref "R8") (pin "1") (pinfunction "1_1") (pintype "passive"))
      (node (ref "R9") (pin "1") (pinfunction "1_1") (pintype "passive"))
      (node (ref "U17") (pin "3") (pinfunction "Vo-_3") (pintype "passive"))
    )
    (net (code "41") (name "Net-(D1-A)") (class "Default")
      (node (ref "D1") (pin "1") (pinfunction "A_1") (pintype "passive"))
      (node (ref "KOUT1") (pin "8") (pinfunction "8_8") (pintype "passive"))
      (node (ref "Q1") (pin "3") (pinfunction "c_3") (pintype "passive"))
    )
    (net (code "42") (name "Net-(D2-A)") (class "Default")
      (node (ref "D2") (pin "1") (pinfunction "A_1") (pintype "passive"))
      (node (ref "KOUT2") (pin "8") (pinfunction "8_8") (pintype "passive"))
      (node (ref "Q2") (pin "3") (pinfunction "c_3") (pintype "passive"))
    )
    (net (code "43") (name "Net-(D3-A)") (class "Default")
      (node (ref "D3") (pin "1") (pinfunction "A_1") (pintype "passive"))
      (node (ref "KOUT3") (pin "8") (pinfunction "8_8") (pintype "passive"))
      (node (ref "Q4") (pin "3") (pinfunction "c_3") (pintype "passive"))
    )
    (net (code "44") (name "Net-(D4-A)") (class "Default")
      (node (ref "D4") (pin "1") (pinfunction "A_1") (pintype "passive"))
      (node (ref "KOUT4") (pin "8") (pinfunction "8_8") (pintype "passive"))
      (node (ref "Q5") (pin "3") (pinfunction "c_3") (pintype "passive"))
    )
    (net (code "45") (name "Net-(D5-A)") (class "Default")
      (node (ref "D5") (pin "1") (pinfunction "A_1") (pintype "passive"))
      (node (ref "R29") (pin "2") (pinfunction "2_2") (pintype "passive"))
    )
    (net (code "46") (name "Net-(D6-A)") (class "Default")
      (node (ref "D6") (pin "1") (pinfunction "A_1") (pintype "passive"))
      (node (ref "R32") (pin "2") (pinfunction "2_2") (pintype "passive"))
    )
    (net (code "47") (name "Net-(Q1-b)") (class "Default")
      (node (ref "C1") (pin "1") (pinfunction "1_1") (pintype "passive"))
      (node (ref "Q1") (pin "1") (pinfunction "b_1") (pintype "passive"))
      (node (ref "R1") (pin "1") (pinfunction "1_1") (pintype "passive"))
    )
    (net (code "48") (name "Net-(Q2-b)") (class "Default")
      (node (ref "C2") (pin "1") (pinfunction "1_1") (pintype "passive"))
      (node (ref "Q2") (pin "1") (pinfunction "b_1") (pintype "passive"))
      (node (ref "R3") (pin "1") (pinfunction "1_1") (pintype "passive"))
    )
    (net (code "49") (name "Net-(Q3-b)") (class "Default")
      (node (ref "Q3") (pin "1") (pinfunction "b_1") (pintype "passive"))
      (node (ref "R5") (pin "1") (pinfunction "1_1") (pintype "passive"))
    )
    (net (code "50") (name "Net-(Q4-b)") (class "Default")
      (node (ref "C3") (pin "1") (pinfunction "1_1") (pintype "passive"))
      (node (ref "Q4") (pin "1") (pinfunction "b_1") (pintype "passive"))
      (node (ref "R16") (pin "1") (pinfunction "1_1") (pintype "passive"))
    )
    (net (code "51") (name "Net-(Q5-b)") (class "Default")
      (node (ref "C4") (pin "1") (pinfunction "1_1") (pintype "passive"))
      (node (ref "Q5") (pin "1") (pinfunction "b_1") (pintype "passive"))
      (node (ref "R17") (pin "1") (pinfunction "1_1") (pintype "passive"))
    )
    (net (code "52") (name "Net-(Q6-b)") (class "Default")
      (node (ref "C5") (pin "1") (pinfunction "1_1") (pintype "passive"))
      (node (ref "Q6") (pin "1") (pinfunction "b_1") (pintype "passive"))
      (node (ref "R20") (pin "1") (pinfunction "1_1") (pintype "passive"))
    )
    (net (code "53") (name "Net-(SB1-1)") (class "Default")
      (node (ref "C6") (pin "1") (pinfunction "1_1") (pintype "passive"))
      (node (ref "R27") (pin "2") (pinfunction "2_2") (pintype "passive"))
      (node (ref "SB1") (pin "3") (pinfunction "1_3") (pintype "passive"))
      (node (ref "SB1") (pin "4") (pinfunction "I1_4") (pintype "passive"))
      (node (ref "U12") (pin "3") (pinfunction "~{MR}_3") (pintype "passive"))
    )
    (net (code "54") (name "Net-(U1-E)") (class "Default")
      (node (ref "R1") (pin "2") (pinfunction "2_2") (pintype "passive"))
      (node (ref "R8") (pin "2") (pinfunction "2_2") (pintype "passive"))
      (node (ref "U1") (pin "3") (pinfunction "E_3") (pintype "passive"))
    )
    (net (code "55") (name "Net-(U1-K)") (class "Default")
      (node (ref "R6") (pin "2") (pinfunction "2_2") (pintype "passive"))
      (node (ref "U1") (pin "2") (pinfunction "K_2") (pintype "passive"))
    )
    (net (code "56") (name "Net-(U2-E)") (class "Default")
      (node (ref "R3") (pin "2") (pinfunction "2_2") (pintype "passive"))
      (node (ref "R9") (pin "2") (pinfunction "2_2") (pintype "passive"))
      (node (ref "U2") (pin "3") (pinfunction "E_3") (pintype "passive"))
    )
    (net (code "57") (name "Net-(U2-K)") (class "Default")
      (node (ref "R7") (pin "2") (pinfunction "2_2") (pintype "passive"))
      (node (ref "U2") (pin "2") (pinfunction "K_2") (pintype "passive"))
    )
    (net (code "58") (name "Net-(U3-E)") (class "Default")
      (node (ref "R11") (pin "2") (pinfunction "2_2") (pintype "passive"))
      (node (ref "R5") (pin "2") (pinfunction "2_2") (pintype "passive"))
      (node (ref "U3") (pin "3") (pinfunction "E_3") (pintype "passive"))
    )
    (net (code "59") (name "Net-(U3-K)") (class "Default")
      (node (ref "R10") (pin "2") (pinfunction "2_2") (pintype "passive"))
      (node (ref "U3") (pin "2") (pinfunction "K_2") (pintype "passive"))
    )
    (net (code "60") (name "Net-(U4-A)") (class "Default")
      (node (ref "R4") (pin "1") (pinfunction "1_1") (pintype "passive"))
      (node (ref "U4") (pin "1") (pinfunction "A_1") (pintype "passive"))
    )
    (net (code "61") (name "Net-(U5-A)") (class "Default")
      (node (ref "R13") (pin "1") (pinfunction "1_1") (pintype "passive"))
      (node (ref "U5") (pin "1") (pinfunction "A_1") (pintype "passive"))
    )
    (net (code "62") (name "Net-(U6-E)") (class "Default")
      (node (ref "R16") (pin "2") (pinfunction "2_2") (pintype "passive"))
      (node (ref "R21") (pin "2") (pinfunction "2_2") (pintype "passive"))
      (node (ref "U6") (pin "3") (pinfunction "E_3") (pintype "passive"))
    )
    (net (code "63") (name "Net-(U6-K)") (class "Default")
      (node (ref "R18") (pin "2") (pinfunction "2_2") (pintype "passive"))
      (node (ref "U6") (pin "2") (pinfunction "K_2") (pintype "passive"))
    )
    (net (code "64") (name "Net-(U7-E)") (class "Default")
      (node (ref "R17") (pin "2") (pinfunction "2_2") (pintype "passive"))
      (node (ref "R22") (pin "2") (pinfunction "2_2") (pintype "passive"))
      (node (ref "U7") (pin "3") (pinfunction "E_3") (pintype "passive"))
    )
    (net (code "65") (name "Net-(U7-K)") (class "Default")
      (node (ref "R19") (pin "2") (pinfunction "2_2") (pintype "passive"))
      (node (ref "U7") (pin "2") (pinfunction "K_2") (pintype "passive"))
    )
    (net (code "66") (name "Net-(U8-A)") (class "Default")
      (node (ref "R15") (pin "1") (pinfunction "1_1") (pintype "passive"))
      (node (ref "U8") (pin "1") (pinfunction "A_1") (pintype "passive"))
    )
    (net (code "67") (name "Net-(U9-E)") (class "Default")
      (node (ref "R20") (pin "2") (pinfunction "2_2") (pintype "passive"))
      (node (ref "R26") (pin "2") (pinfunction "2_2") (pintype "passive"))
      (node (ref "U9") (pin "3") (pinfunction "E_3") (pintype "passive"))
    )
    (net (code "68") (name "Net-(U9-K)") (class "Default")
      (node (ref "R25") (pin "2") (pinfunction "2_2") (pintype "passive"))
      (node (ref "U9") (pin "2") (pinfunction "K_2") (pintype "passive"))
    )
    (net (code "69") (name "Net-(U10-A)") (class "Default")
      (node (ref "R24") (pin "1") (pinfunction "1_1") (pintype "passive"))
      (node (ref "U10") (pin "1") (pinfunction "A_1") (pintype "passive"))
    )
    (net (code "70") (name "Net-(U13-VCAP)") (class "Default")
      (node (ref "C11") (pin "2") (pinfunction "2_2") (pintype "passive"))
      (node (ref "U13") (pin "6") (pinfunction "VCAP_6") (pintype "power_in"))
    )
    (net (code "71") (name "Net-(U14-A)") (class "Default")
      (node (ref "R30") (pin "1") (pinfunction "1_1") (pintype "passive"))
      (node (ref "U14") (pin "6") (pinfunction "A_6") (pintype "passive"))
      (node (ref "U15") (pin "8") (pinfunction "A1_8") (pintype "passive"))
    )
    (net (code "72") (name "Net-(U14-B)") (class "Default")
      (node (ref "R33") (pin "2") (pinfunction "2_2") (pintype "passive"))
      (node (ref "U14") (pin "7") (pinfunction "B_7") (pintype "passive"))
      (node (ref "U15") (pin "5") (pinfunction "B1_5") (pintype "passive"))
    )
    (net (code "73") (name "Net-(U14-VO)") (class "Default")
      (node (ref "R30") (pin "2") (pinfunction "2_2") (pintype "passive"))
      (node (ref "U14") (pin "8") (pinfunction "VO_8") (pintype "passive"))
    )
    (net (code "74") (name "Net-(U16-Vin-)") (class "Default")
      (node (ref "C20") (pin "2") (pinfunction "2_2") (pintype "passive"))
      (node (ref "P3") (pin "1") (pinfunction "1_1") (pintype "passive"))
      (node (ref "U16") (pin "2") (pinfunction "Vin-_2") (pintype "input"))
      (node (ref "U17") (pin "2") (pinfunction "Vin-_2") (pintype "input"))
    )
    (net (code "75") (name "VCC") (class "Default")
      (node (ref "C10") (pin "2") (pinfunction "2_2") (pintype "passive"))
      (node (ref "C12") (pin "2") (pinfunction "2_2") (pintype "passive"))
      (node (ref "C13") (pin "2") (pinfunction "2_2") (pintype "passive"))
      (node (ref "C14") (pin "1") (pinfunction "1_1") (pintype "passive"))
      (node (ref "C15") (pin "2") (pinfunction "2_2") (pintype "passive"))
      (node (ref "C16") (pin "1") (pinfunction "1_1") (pintype "passive"))
      (node (ref "C17") (pin "2") (pinfunction "2_2") (pintype "passive"))
      (node (ref "C18") (pin "1") (pinfunction "1_1") (pintype "passive"))
      (node (ref "C21") (pin "1") (pinfunction "1_1") (pintype "passive"))
      (node (ref "C7") (pin "2") (pinfunction "2_2") (pintype "passive"))
      (node (ref "C8") (pin "2") (pinfunction "2_2") (pintype "passive"))
      (node (ref "C9") (pin "2") (pinfunction "2_2") (pintype "passive"))
      (node (ref "D7") (pin "2") (pinfunction "K_2") (pintype "passive"))
      (node (ref "P2") (pin "1") (pinfunction "1_1") (pintype "passive"))
      (node (ref "R12") (pin "1") (pinfunction "1_1") (pintype "passive"))
      (node (ref "R14") (pin "1") (pinfunction "1_1") (pintype "passive"))
      (node (ref "R2") (pin "1") (pinfunction "1_1") (pintype "passive"))
      (node (ref "R23") (pin "1") (pinfunction "1_1") (pintype "passive"))
      (node (ref "R27") (pin "1") (pinfunction "1_1") (pintype "passive"))
      (node (ref "R28") (pin "1") (pinfunction "1_1") (pintype "passive"))
      (node (ref "R32") (pin "1") (pinfunction "1_1") (pintype "passive"))
      (node (ref "R34") (pin "1") (pinfunction "1_1") (pintype "passive"))
      (node (ref "U1") (pin "1") (pinfunction "A_1") (pintype "passive"))
      (node (ref "U11") (pin "12") (pinfunction "VCC_12") (pintype "input"))
      (node (ref "U12") (pin "5") (pinfunction "VCC_5") (pintype "passive"))
      (node (ref "U13") (pin "12") (pinfunction "VDDA_12") (pintype "power_in"))
      (node (ref "U13") (pin "29") (pinfunction "VDDIO_2_29") (pintype "power_in"))
      (node (ref "U13") (pin "7") (pinfunction "VDD_7") (pintype "power_in"))
      (node (ref "U13") (pin "8") (pinfunction "VDDIO_1_8") (pintype "power_in"))
      (node (ref "U14") (pin "4") (pinfunction "VCC_4") (pintype "passive"))
      (node (ref "U16") (pin "4") (pinfunction "Vo+_4") (pintype "power_in"))
      (node (ref "U2") (pin "1") (pinfunction "A_1") (pintype "passive"))
      (node (ref "U3") (pin "1") (pinfunction "A_1") (pintype "passive"))
      (node (ref "U6") (pin "1") (pinfunction "A_1") (pintype "passive"))
      (node (ref "U7") (pin "1") (pinfunction "A_1") (pintype "passive"))
      (node (ref "U9") (pin "1") (pinfunction "A_1") (pintype "passive"))
    )
    (net (code "76") (name "unconnected-(KOUT1-Pad2)") (class "Default")
      (node (ref "KOUT1") (pin "2") (pinfunction "2_2") (pintype "passive"))
    )
    (net (code "77") (name "unconnected-(KOUT1-Pad7)") (class "Default")
      (node (ref "KOUT1") (pin "7") (pinfunction "7_7") (pintype "passive"))
    )
    (net (code "78") (name "unconnected-(KOUT2-Pad2)") (class "Default")
      (node (ref "KOUT2") (pin "2") (pinfunction "2_2") (pintype "passive"))
    )
    (net (code "79") (name "unconnected-(KOUT2-Pad7)") (class "Default")
      (node (ref "KOUT2") (pin "7") (pinfunction "7_7") (pintype "passive"))
    )
    (net (code "80") (name "unconnected-(KOUT3-Pad2)") (class "Default")
      (node (ref "KOUT3") (pin "2") (pinfunction "2_2") (pintype "passive"))
    )
    (net (code "81") (name "unconnected-(KOUT3-Pad7)") (class "Default")
      (node (ref "KOUT3") (pin "7") (pinfunction "7_7") (pintype "passive"))
    )
    (net (code "82") (name "unconnected-(KOUT4-Pad2)") (class "Default")
      (node (ref "KOUT4") (pin "2") (pinfunction "2_2") (pintype "passive"))
    )
    (net (code "83") (name "unconnected-(KOUT4-Pad7)") (class "Default")
      (node (ref "KOUT4") (pin "7") (pinfunction "7_7") (pintype "passive"))
    )
    (net (code "84") (name "unconnected-(P1-Pad1)") (class "Default")
      (node (ref "P1") (pin "1") (pinfunction "1_1") (pintype "passive"))
    )
    (net (code "85") (name "unconnected-(P1-Pad2)") (class "Default")
      (node (ref "P1") (pin "2") (pinfunction "2_2") (pintype "passive"))
    )
    (net (code "86") (name "unconnected-(P1-Pad5)") (class "Default")
      (node (ref "P1") (pin "5") (pinfunction "5_5") (pintype "passive"))
    )
    (net (code "87") (name "unconnected-(P1-Pad6)") (class "Default")
      (node (ref "P1") (pin "6") (pinfunction "6_6") (pintype "passive"))
    )
    (net (code "88") (name "unconnected-(P1-Pad8)") (class "Default")
      (node (ref "P1") (pin "8") (pinfunction "8_8") (pintype "passive"))
    )
    (net (code "89") (name "unconnected-(P1-Pad9)") (class "Default")
      (node (ref "P1") (pin "9") (pinfunction "9_9") (pintype "passive"))
    )
    (net (code "90") (name "unconnected-(P1-Pad11)") (class "Default")
      (node (ref "P1") (pin "11") (pinfunction "11_11") (pintype "passive"))
    )
    (net (code "91") (name "unconnected-(P1-Pad12)") (class "Default")
      (node (ref "P1") (pin "12") (pinfunction "12_12") (pintype "passive"))
    )
    (net (code "92") (name "unconnected-(P1-Pad13)") (class "Default")
      (node (ref "P1") (pin "13") (pinfunction "13_13") (pintype "passive"))
    )
    (net (code "93") (name "unconnected-(P1-Pad14)") (class "Default")
      (node (ref "P1") (pin "14") (pinfunction "14_14") (pintype "passive"))
    )
    (net (code "94") (name "unconnected-(P1-Pad15)") (class "Default")
      (node (ref "P1") (pin "15") (pinfunction "15_15") (pintype "passive"))
    )
    (net (code "95") (name "unconnected-(P1-Pad17)") (class "Default")
      (node (ref "P1") (pin "17") (pinfunction "17_17") (pintype "passive"))
    )
    (net (code "96") (name "unconnected-(P1-Pad18)") (class "Default")
      (node (ref "P1") (pin "18") (pinfunction "18_18") (pintype "passive"))
    )
    (net (code "97") (name "unconnected-(P1-Pad23)") (class "Default")
      (node (ref "P1") (pin "23") (pinfunction "23_23") (pintype "passive"))
    )
    (net (code "98") (name "unconnected-(P1-Pad24)") (class "Default")
      (node (ref "P1") (pin "24") (pinfunction "24_24") (pintype "passive"))
    )
    (net (code "99") (name "unconnected-(P1-Pad25)") (class "Default")
      (node (ref "P1") (pin "25") (pinfunction "25_25") (pintype "passive"))
    )
    (net (code "100") (name "unconnected-(P1-Pad27)") (class "Default")
      (node (ref "P1") (pin "27") (pinfunction "27_27") (pintype "passive"))
    )
    (net (code "101") (name "unconnected-(P1-Pad28)") (class "Default")
      (node (ref "P1") (pin "28") (pinfunction "28_28") (pintype "passive"))
    )
    (net (code "102") (name "unconnected-(P1-Pad29)") (class "Default")
      (node (ref "P1") (pin "29") (pinfunction "29_29") (pintype "passive"))
    )
    (net (code "103") (name "unconnected-(P1-Pad30)") (class "Default")
      (node (ref "P1") (pin "30") (pinfunction "30_30") (pintype "passive"))
    )
    (net (code "104") (name "unconnected-(P1-Pad39)") (class "Default")
      (node (ref "P1") (pin "39") (pinfunction "39_39") (pintype "passive"))
    )
    (net (code "105") (name "unconnected-(P1-Pad40)") (class "Default")
      (node (ref "P1") (pin "40") (pinfunction "40_40") (pintype "passive"))
    )
    (net (code "106") (name "unconnected-(P1-Pad41)") (class "Default")
      (node (ref "P1") (pin "41") (pinfunction "41_41") (pintype "passive"))
    )
    (net (code "107") (name "unconnected-(P1-Pad42)") (class "Default")
      (node (ref "P1") (pin "42") (pinfunction "42_42") (pintype "passive"))
    )
    (net (code "108") (name "unconnected-(P1-Pad43)") (class "Default")
      (node (ref "P1") (pin "43") (pinfunction "43_43") (pintype "passive"))
    )
    (net (code "109") (name "unconnected-(P1-Pad44)") (class "Default")
      (node (ref "P1") (pin "44") (pinfunction "44_44") (pintype "passive"))
    )
    (net (code "110") (name "unconnected-(U11-KEY+-Pad26)") (class "Default")
      (node (ref "U11") (pin "26") (pinfunction "KEY+_26") (pintype "passive"))
    )
    (net (code "111") (name "unconnected-(U11-KEY--Pad15)") (class "Default")
      (node (ref "U11") (pin "15") (pinfunction "KEY-_15") (pintype "passive"))
    )
    (net (code "112") (name "unconnected-(U11-LED-Pad16)") (class "Default")
      (node (ref "U11") (pin "16") (pinfunction "LED_16") (pintype "output"))
    )
    (net (code "113") (name "unconnected-(U11-LED-Pad23)") (class "Default")
      (node (ref "U11") (pin "23") (pinfunction "LED_23") (pintype "output"))
    )
    (net (code "114") (name "unconnected-(U11-LEDCON-Pad14)") (class "Default")
      (node (ref "U11") (pin "14") (pinfunction "LEDCON_14") (pintype "passive"))
    )
    (net (code "115") (name "unconnected-(U11-NC-Pad3)") (class "Default")
      (node (ref "U11") (pin "3") (pinfunction "NC_3") (pintype "passive"))
    )
    (net (code "116") (name "unconnected-(U11-NC-Pad4)") (class "Default")
      (node (ref "U11") (pin "4") (pinfunction "NC_4") (pintype "passive"))
    )
    (net (code "117") (name "unconnected-(U11-NC-Pad5)") (class "Default")
      (node (ref "U11") (pin "5") (pinfunction "NC_5") (pintype "passive"))
    )
    (net (code "118") (name "unconnected-(U11-NC-Pad6)") (class "Default")
      (node (ref "U11") (pin "6") (pinfunction "NC_6") (pintype "passive"))
    )
    (net (code "119") (name "unconnected-(U11-NC-Pad7)") (class "Default")
      (node (ref "U11") (pin "7") (pinfunction "NC_7") (pintype "passive"))
    )
    (net (code "120") (name "unconnected-(U11-NC-Pad8)") (class "Default")
      (node (ref "U11") (pin "8") (pinfunction "NC_8") (pintype "passive"))
    )
    (net (code "121") (name "unconnected-(U11-NC-Pad9)") (class "Default")
      (node (ref "U11") (pin "9") (pinfunction "NC_9") (pintype "passive"))
    )
    (net (code "122") (name "unconnected-(U11-NC-Pad10)") (class "Default")
      (node (ref "U11") (pin "10") (pinfunction "NC_10") (pintype "passive"))
    )
    (net (code "123") (name "unconnected-(U11-NC-Pad19)") (class "Default")
      (node (ref "U11") (pin "19") (pinfunction "NC_19") (pintype "passive"))
    )
    (net (code "124") (name "unconnected-(U11-NC-Pad20)") (class "Default")
      (node (ref "U11") (pin "20") (pinfunction "NC_20") (pintype "passive"))
    )
    (net (code "125") (name "unconnected-(U11-NC-Pad21)") (class "Default")
      (node (ref "U11") (pin "21") (pinfunction "NC_21") (pintype "passive"))
    )
    (net (code "126") (name "unconnected-(U11-NC-Pad22)") (class "Default")
      (node (ref "U11") (pin "22") (pinfunction "NC_22") (pintype "passive"))
    )
    (net (code "127") (name "unconnected-(U11-NC-Pad25)") (class "Default")
      (node (ref "U11") (pin "25") (pinfunction "NC_25") (pintype "passive"))
    )
    (net (code "128") (name "unconnected-(U11-STATUS-Pad17)") (class "Default")
      (node (ref "U11") (pin "17") (pinfunction "STATUS_17") (pintype "output"))
    )
    (net (code "129") (name "unconnected-(U11-STATUS-Pad24)") (class "Default")
      (node (ref "U11") (pin "24") (pinfunction "STATUS_24") (pintype "output"))
    )
    (net (code "130") (name "unconnected-(U13-AIN6{slash}PB6-Pad15)") (class "Default")
      (node (ref "U13") (pin "15") (pinfunction "AIN6/PB6_15") (pintype "bidirectional"))
    )
    (net (code "131") (name "unconnected-(U13-AIN7{slash}PB7-Pad14)") (class "Default")
      (node (ref "U13") (pin "14") (pinfunction "AIN7/PB7_14") (pintype "bidirectional"))
    )
    (net (code "132") (name "unconnected-(U13-AIN9{slash}PE6-Pad22)") (class "Default")
      (node (ref "U13") (pin "22") (pinfunction "AIN9/PE6_22") (pintype "bidirectional"))
    )
    (net (code "133") (name "unconnected-(U13-PC7_(HS){slash}SPI_MISO-Pad31)") (class "Default")
      (node (ref "U13") (pin "31") (pinfunction "PC7_(HS)/SPI_MISO_31") (pintype "bidirectional"))
    )
    (net (code "134") (name "unconnected-(U13-PD0_(HS){slash}TIM3_CH2_[TIM1_BKIN]_[CLK_CCO]-Pad37)") (class "Default")
      (node (ref "U13") (pin "37") (pinfunction "PD0_(HS)/TIM3_CH2_[TIM1_BKIN]_[CLK_CCO]_37") (pintype "bidirectional"))
    )
    (net (code "135") (name "unconnected-(U13-PD2_(HS){slash}TIM3_CH1_[TIM2_CH3]-Pad39)") (class "Default")
      (node (ref "U13") (pin "39") (pinfunction "PD2_(HS)/TIM3_CH1_[TIM2_CH3]_39") (pintype "bidirectional"))
    )
    (net (code "136") (name "unconnected-(U13-PE0_(HS){slash}CLK_CCO-Pad36)") (class "Default")
      (node (ref "U13") (pin "36") (pinfunction "PE0_(HS)/CLK_CCO_36") (pintype "bidirectional"))
    )
    (net (code "137") (name "unconnected-(U13-PE1_(T){slash}I2C_SCL-Pad35)") (class "Default")
      (node (ref "U13") (pin "35") (pinfunction "PE1_(T)/I2C_SCL_35") (pintype "bidirectional"))
    )
    (net (code "138") (name "unconnected-(U13-PE2_(T){slash}I2C_SDA-Pad34)") (class "Default")
      (node (ref "U13") (pin "34") (pinfunction "PE2_(T)/I2C_SDA_34") (pintype "bidirectional"))
    )
    (net (code "139") (name "unconnected-(U13-PE5{slash}SPI_NSS-Pad23)") (class "Default")
      (node (ref "U13") (pin "23") (pinfunction "PE5/SPI_NSS_23") (pintype "bidirectional"))
    )
    (net (code "140") (name "unconnected-(U13-PG0{slash}CAN_TX-Pad32)") (class "Default")
      (node (ref "U13") (pin "32") (pinfunction "PG0/CAN_TX_32") (pintype "bidirectional"))
    )
    (net (code "141") (name "unconnected-(U13-PG1{slash}CAN_RX-Pad33)") (class "Default")
      (node (ref "U13") (pin "33") (pinfunction "PG1/CAN_RX_33") (pintype "bidirectional"))
    )
    (net (code "142") (name "unconnected-(U13-UART1_CK-Pad11)") (class "Default")
      (node (ref "U13") (pin "11") (pinfunction "UART1_CK_11") (pintype "bidirectional"))
    )
  )
)
